# EMoC_Hardware.net
KiCad netlist of a schematic drawn in Altium Designer
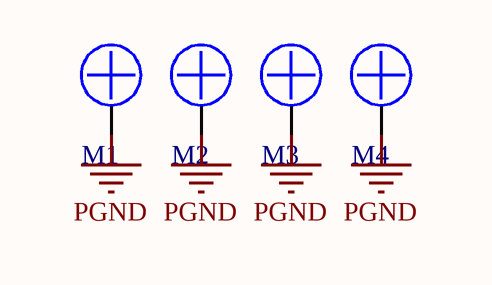
[diagram p0: EMoC_Hardware.SchDoc]

(export (version "E")
  (design (tool "Eeschema 10.0.6"))
  (components
    (comp (ref "M1")
      (value "Mounting_Screw")
      (footprint "MOUNT_HOLE_3.2")
      (libsource (lib "libysk") (part "Mounting_Screw"))
    )
    (comp (ref "M2")
      (value "Mounting_Screw")
      (footprint "MOUNT_HOLE_3.2")
      (libsource (lib "libysk") (part "Mounting_Screw"))
    )
    (comp (ref "M3")
      (value "Mounting_Screw")
      (footprint "MOUNT_HOLE_3.2")
      (libsource (lib "libysk") (part "Mounting_Screw"))
    )
    (comp (ref "M4")
      (value "Mounting_Screw")
      (footprint "MOUNT_HOLE_3.2")
      (libsource (lib "libysk") (part "Mounting_Screw"))
    )
  )
  (nets
    (net (code "1") (name "PGND") (class "Default")
      (node (ref "M1") (pin "1") (pinfunction "1_1") (pintype "passive"))
      (node (ref "M2") (pin "1") (pinfunction "1_1") (pintype "passive"))
      (node (ref "M3") (pin "1") (pinfunction "1_1") (pintype "passive"))
      (node (ref "M4") (pin "1") (pinfunction "1_1") (pintype "passive"))
    )
  )
)
